# design.net
KiCad netlist of a schematic drawn in Altium Designer
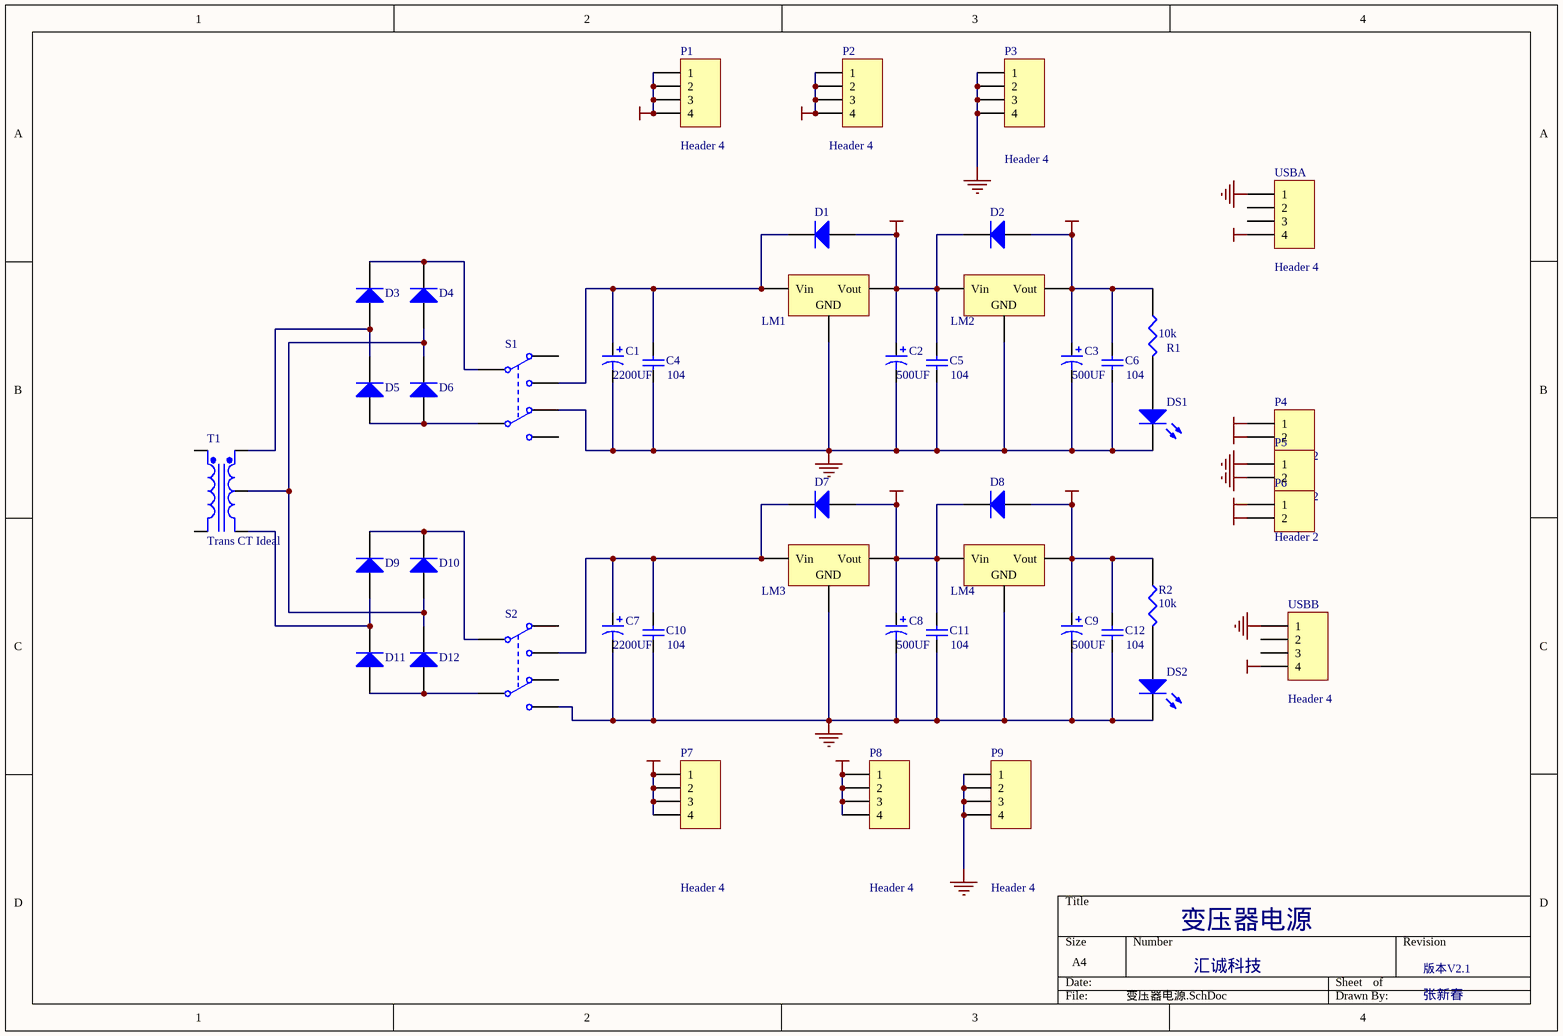
[diagram p0: 变压器电源.SchDoc]

(export (version "E")
  (design (tool "Eeschema 10.0.6"))
  (components
    (comp (ref "C1")
      (value "2200UF")
      (footprint "C 2200/50")
      (description "Polarized Capacitor (Radial)")
      (fields (field (name "PUBLISHER") "Altium Limited"))
      (libsource (lib "Miscellaneous Devices") (part "Cap Pol1"))
    )
    (comp (ref "C2")
      (value "500UF")
      (footprint "C 220/50")
      (description "Polarized Capacitor (Radial)")
      (fields (field (name "PUBLISHER") "Altium Limited"))
      (libsource (lib "Miscellaneous Devices") (part "Cap Pol1"))
    )
    (comp (ref "C3")
      (value "500UF")
      (footprint "C 220/50")
      (description "Polarized Capacitor (Radial)")
      (fields (field (name "PUBLISHER") "Altium Limited"))
      (libsource (lib "Miscellaneous Devices") (part "Cap Pol1"))
    )
    (comp (ref "C4")
      (value "104")
      (footprint "HDR1X2")
      (description "Capacitor")
      (fields (field (name "PUBLISHER") "Altium Limited"))
      (libsource (lib "Miscellaneous Devices") (part "Cap"))
    )
    (comp (ref "C5")
      (value "104")
      (footprint "HDR1X2")
      (description "Capacitor")
      (fields (field (name "PUBLISHER") "Altium Limited"))
      (libsource (lib "Miscellaneous Devices") (part "Cap"))
    )
    (comp (ref "C6")
      (value "104")
      (footprint "HDR1X2")
      (description "Capacitor")
      (fields (field (name "PUBLISHER") "Altium Limited"))
      (libsource (lib "Miscellaneous Devices") (part "Cap"))
    )
    (comp (ref "C7")
      (value "2200UF")
      (footprint "C 2200/50")
      (description "Polarized Capacitor (Radial)")
      (fields (field (name "PUBLISHER") "Altium Limited"))
      (libsource (lib "Miscellaneous Devices") (part "Cap Pol1"))
    )
    (comp (ref "C8")
      (value "500UF")
      (footprint "C 220/50")
      (description "Polarized Capacitor (Radial)")
      (fields (field (name "PUBLISHER") "Altium Limited"))
      (libsource (lib "Miscellaneous Devices") (part "Cap Pol1"))
    )
    (comp (ref "C9")
      (value "500UF")
      (footprint "C 220/50")
      (description "Polarized Capacitor (Radial)")
      (fields (field (name "PUBLISHER") "Altium Limited"))
      (libsource (lib "Miscellaneous Devices") (part "Cap Pol1"))
    )
    (comp (ref "C10")
      (value "104")
      (footprint "HDR1X2")
      (description "Capacitor")
      (fields (field (name "PUBLISHER") "Altium Limited"))
      (libsource (lib "Miscellaneous Devices") (part "Cap"))
    )
    (comp (ref "C11")
      (value "104")
      (footprint "HDR1X2")
      (description "Capacitor")
      (fields (field (name "PUBLISHER") "Altium Limited"))
      (libsource (lib "Miscellaneous Devices") (part "Cap"))
    )
    (comp (ref "C12")
      (value "104")
      (footprint "HDR1X2")
      (description "Capacitor")
      (fields (field (name "PUBLISHER") "Altium Limited"))
      (libsource (lib "Miscellaneous Devices") (part "Cap"))
    )
    (comp (ref "D1")
      (value "~")
      (footprint "DIO10.46-5.3x2.8")
      (description "1 Amp General Purpose Rectifier")
      (fields (field (name "PUBLISHER") "Altium Limited"))
      (libsource (lib "Miscellaneous Devices") (part "Diode 1N4007"))
    )
    (comp (ref "D2")
      (value "~")
      (footprint "DIO10.46-5.3x2.8")
      (description "1 Amp General Purpose Rectifier")
      (fields (field (name "PUBLISHER") "Altium Limited"))
      (libsource (lib "Miscellaneous Devices") (part "Diode 1N4007"))
    )
    (comp (ref "D3")
      (value "~")
      (footprint "DIO10.46-5.3x2.8")
      (description "1 Amp General Purpose Rectifier")
      (fields (field (name "PUBLISHER") "Altium Limited"))
      (libsource (lib "Miscellaneous Devices") (part "Diode 1N4007"))
    )
    (comp (ref "D4")
      (value "~")
      (footprint "DIO10.46-5.3x2.8")
      (description "1 Amp General Purpose Rectifier")
      (fields (field (name "PUBLISHER") "Altium Limited"))
      (libsource (lib "Miscellaneous Devices") (part "Diode 1N4007"))
    )
    (comp (ref "D5")
      (value "~")
      (footprint "DIO10.46-5.3x2.8")
      (description "1 Amp General Purpose Rectifier")
      (fields (field (name "PUBLISHER") "Altium Limited"))
      (libsource (lib "Miscellaneous Devices") (part "Diode 1N4007"))
    )
    (comp (ref "D6")
      (value "~")
      (footprint "DIO10.46-5.3x2.8")
      (description "1 Amp General Purpose Rectifier")
      (fields (field (name "PUBLISHER") "Altium Limited"))
      (libsource (lib "Miscellaneous Devices") (part "Diode 1N4007"))
    )
    (comp (ref "D7")
      (value "~")
      (footprint "DIO10.46-5.3x2.8")
      (description "1 Amp General Purpose Rectifier")
      (fields (field (name "PUBLISHER") "Altium Limited"))
      (libsource (lib "Miscellaneous Devices") (part "Diode 1N4007"))
    )
    (comp (ref "D8")
      (value "~")
      (footprint "DIO10.46-5.3x2.8")
      (description "1 Amp General Purpose Rectifier")
      (fields (field (name "PUBLISHER") "Altium Limited"))
      (libsource (lib "Miscellaneous Devices") (part "Diode 1N4007"))
    )
    (comp (ref "D9")
      (value "~")
      (footprint "DIO10.46-5.3x2.8")
      (description "1 Amp General Purpose Rectifier")
      (fields (field (name "PUBLISHER") "Altium Limited"))
      (libsource (lib "Miscellaneous Devices") (part "Diode 1N4007"))
    )
    (comp (ref "D10")
      (value "~")
      (footprint "DIO10.46-5.3x2.8")
      (description "1 Amp General Purpose Rectifier")
      (fields (field (name "PUBLISHER") "Altium Limited"))
      (libsource (lib "Miscellaneous Devices") (part "Diode 1N4007"))
    )
    (comp (ref "D11")
      (value "~")
      (footprint "DIO10.46-5.3x2.8")
      (description "1 Amp General Purpose Rectifier")
      (fields (field (name "PUBLISHER") "Altium Limited"))
      (libsource (lib "Miscellaneous Devices") (part "Diode 1N4007"))
    )
    (comp (ref "D12")
      (value "~")
      (footprint "DIO10.46-5.3x2.8")
      (description "1 Amp General Purpose Rectifier")
      (fields (field (name "PUBLISHER") "Altium Limited"))
      (libsource (lib "Miscellaneous Devices") (part "Diode 1N4007"))
    )
    (comp (ref "DS1")
      (value "~")
      (footprint "HDR1X2")
      (description "Typical INFRARED GaAs LED")
      (fields (field (name "PUBLISHER") "Altium Limited"))
      (libsource (lib "Miscellaneous Devices") (part "LED0"))
    )
    (comp (ref "DS2")
      (value "~")
      (footprint "HDR1X2")
      (description "Typical INFRARED GaAs LED")
      (fields (field (name "PUBLISHER") "Altium Limited"))
      (libsource (lib "Miscellaneous Devices") (part "LED0"))
    )
    (comp (ref "LM1")
      (value "~")
      (footprint "wyk")
      (description "Voltage Regulator")
      (fields (field (name "PUBLISHER") "Altium Limited"))
      (libsource (lib "Miscellaneous Devices") (part "Volt Reg"))
    )
    (comp (ref "LM2")
      (value "~")
      (footprint "wyk")
      (description "Voltage Regulator")
      (fields (field (name "PUBLISHER") "Altium Limited"))
      (libsource (lib "Miscellaneous Devices") (part "Volt Reg"))
    )
    (comp (ref "LM3")
      (value "~")
      (footprint "wyk")
      (description "Voltage Regulator")
      (fields (field (name "PUBLISHER") "Altium Limited"))
      (libsource (lib "Miscellaneous Devices") (part "Volt Reg"))
    )
    (comp (ref "LM4")
      (value "~")
      (footprint "wyk")
      (description "Voltage Regulator")
      (fields (field (name "PUBLISHER") "Altium Limited"))
      (libsource (lib "Miscellaneous Devices") (part "Volt Reg"))
    )
    (comp (ref "P1")
      (value "Header 4")
      (footprint "HDR1X4")
      (description "Header, 4-Pin")
      (fields (field (name "PUBLISHER") "Altium Limited"))
      (libsource (lib "Miscellaneous Connectors") (part "Header 4"))
    )
    (comp (ref "P2")
      (value "Header 4")
      (footprint "HDR1X4")
      (description "Header, 4-Pin")
      (fields (field (name "PUBLISHER") "Altium Limited"))
      (libsource (lib "Miscellaneous Connectors") (part "Header 4"))
    )
    (comp (ref "P3")
      (value "Header 4")
      (footprint "HDR1X4")
      (description "Header, 4-Pin")
      (fields (field (name "PUBLISHER") "Altium Limited"))
      (libsource (lib "Miscellaneous Connectors") (part "Header 4"))
    )
    (comp (ref "P4")
      (value "Header 2")
      (footprint "PCBComponent_1")
      (description "Header, 2-Pin")
      (fields (field (name "PUBLISHER") "Altium Limited"))
      (libsource (lib "Miscellaneous Connectors") (part "Header 2"))
    )
    (comp (ref "P5")
      (value "Header 2")
      (footprint "PCBComponent_1")
      (description "Header, 2-Pin")
      (fields (field (name "PUBLISHER") "Altium Limited"))
      (libsource (lib "Miscellaneous Connectors") (part "Header 2"))
    )
    (comp (ref "P6")
      (value "Header 2")
      (footprint "PCBComponent_1")
      (description "Header, 2-Pin")
      (fields (field (name "PUBLISHER") "Altium Limited"))
      (libsource (lib "Miscellaneous Connectors") (part "Header 2"))
    )
    (comp (ref "P7")
      (value "Header 4")
      (footprint "HDR1X4")
      (description "Header, 4-Pin")
      (fields (field (name "PUBLISHER") "Altium Limited"))
      (libsource (lib "Miscellaneous Connectors") (part "Header 4"))
    )
    (comp (ref "P8")
      (value "Header 4")
      (footprint "HDR1X4")
      (description "Header, 4-Pin")
      (fields (field (name "PUBLISHER") "Altium Limited"))
      (libsource (lib "Miscellaneous Connectors") (part "Header 4"))
    )
    (comp (ref "P9")
      (value "Header 4")
      (footprint "HDR1X4")
      (description "Header, 4-Pin")
      (fields (field (name "PUBLISHER") "Altium Limited"))
      (libsource (lib "Miscellaneous Connectors") (part "Header 4"))
    )
    (comp (ref "R1") (value "10k") (footprint "HDR1X2") (libsource (lib "*") (part "RES1")))
    (comp (ref "R2") (value "10k") (footprint "HDR1X2") (libsource (lib "*") (part "RES1")))
    (comp (ref "S1")
      (value "~")
      (footprint "DPDT-6")
      (description "Switch")
      (fields (field (name "PUBLISHER") "Altium Limited"))
      (libsource (lib "Miscellaneous Devices") (part "SW DPDT"))
    )
    (comp (ref "S2")
      (value "~")
      (footprint "DPDT-6")
      (description "Switch")
      (fields (field (name "PUBLISHER") "Altium Limited"))
      (libsource (lib "Miscellaneous Devices") (part "SW DPDT"))
    )
    (comp (ref "T1")
      (value "Trans CT Ideal")
      (footprint "T")
      (description "Center-Tapped Transformer (Ideal)")
      (fields (field (name "PUBLISHER") "Altium Limited"))
      (libsource (lib "Miscellaneous Devices") (part "Trans CT Ideal"))
    )
    (comp (ref "USBA")
      (value "Header 4")
      (footprint "HDR1X4")
      (description "Header, 4-Pin")
      (fields (field (name "PUBLISHER") "Altium Limited"))
      (libsource (lib "Miscellaneous Connectors") (part "Header 4"))
    )
    (comp (ref "USBB")
      (value "Header 4")
      (footprint "HDR1X4")
      (description "Header, 4-Pin")
      (fields (field (name "PUBLISHER") "Altium Limited"))
      (libsource (lib "Miscellaneous Connectors") (part "Header 4"))
    )
  )
  (nets
    (net (code "1") (name "A05") (class "Default")
      (node (ref "C3") (pin "1") (pinfunction "1_1") (pintype "passive"))
      (node (ref "C6") (pin "2") (pinfunction "2_2") (pintype "passive"))
      (node (ref "D2") (pin "1") (pinfunction "A_1") (pintype "passive"))
      (node (ref "LM2") (pin "3") (pinfunction "Vout_3") (pintype "passive"))
      (node (ref "P2") (pin "1") (pinfunction "1_1") (pintype "passive"))
      (node (ref "P2") (pin "2") (pinfunction "2_2") (pintype "passive"))
      (node (ref "P2") (pin "3") (pinfunction "3_3") (pintype "passive"))
      (node (ref "P2") (pin "4") (pinfunction "4_4") (pintype "passive"))
      (node (ref "P4") (pin "2") (pinfunction "2_2") (pintype "passive"))
      (node (ref "R1") (pin "1") (pinfunction "1_1") (pintype "passive"))
      (node (ref "USBA") (pin "4") (pinfunction "4_4") (pintype "passive"))
    )
    (net (code "2") (name "A12") (class "Default")
      (node (ref "C2") (pin "1") (pinfunction "1_1") (pintype "passive"))
      (node (ref "C5") (pin "2") (pinfunction "2_2") (pintype "passive"))
      (node (ref "D1") (pin "1") (pinfunction "A_1") (pintype "passive"))
      (node (ref "D2") (pin "2") (pinfunction "K_2") (pintype "passive"))
      (node (ref "LM1") (pin "3") (pinfunction "Vout_3") (pintype "passive"))
      (node (ref "LM2") (pin "1") (pinfunction "Vin_1") (pintype "passive"))
      (node (ref "P1") (pin "1") (pinfunction "1_1") (pintype "passive"))
      (node (ref "P1") (pin "2") (pinfunction "2_2") (pintype "passive"))
      (node (ref "P1") (pin "3") (pinfunction "3_3") (pintype "passive"))
      (node (ref "P1") (pin "4") (pinfunction "4_4") (pintype "passive"))
      (node (ref "P4") (pin "1") (pinfunction "1_1") (pintype "passive"))
    )
    (net (code "3") (name "AGND") (class "Default")
      (node (ref "C1") (pin "2") (pinfunction "2_2") (pintype "passive"))
      (node (ref "C2") (pin "2") (pinfunction "2_2") (pintype "passive"))
      (node (ref "C3") (pin "2") (pinfunction "2_2") (pintype "passive"))
      (node (ref "C4") (pin "1") (pinfunction "1_1") (pintype "passive"))
      (node (ref "C5") (pin "1") (pinfunction "1_1") (pintype "passive"))
      (node (ref "C6") (pin "1") (pinfunction "1_1") (pintype "passive"))
      (node (ref "DS1") (pin "2") (pinfunction "K_2") (pintype "passive"))
      (node (ref "LM1") (pin "2") (pinfunction "GND_2") (pintype "passive"))
      (node (ref "LM2") (pin "2") (pinfunction "GND_2") (pintype "passive"))
      (node (ref "P3") (pin "1") (pinfunction "1_1") (pintype "passive"))
      (node (ref "P3") (pin "2") (pinfunction "2_2") (pintype "passive"))
      (node (ref "P3") (pin "3") (pinfunction "3_3") (pintype "passive"))
      (node (ref "P3") (pin "4") (pinfunction "4_4") (pintype "passive"))
      (node (ref "P5") (pin "2") (pinfunction "2_2") (pintype "passive"))
      (node (ref "S1") (pin "4") (pinfunction "NC2_4") (pintype "passive"))
      (node (ref "USBB") (pin "1") (pinfunction "1_1") (pintype "passive"))
    )
    (net (code "4") (name "B05") (class "Default")
      (node (ref "C12") (pin "2") (pinfunction "2_2") (pintype "passive"))
      (node (ref "C9") (pin "1") (pinfunction "1_1") (pintype "passive"))
      (node (ref "D8") (pin "1") (pinfunction "A_1") (pintype "passive"))
      (node (ref "LM4") (pin "3") (pinfunction "Vout_3") (pintype "passive"))
      (node (ref "P6") (pin "1") (pinfunction "1_1") (pintype "passive"))
      (node (ref "P8") (pin "1") (pinfunction "1_1") (pintype "passive"))
      (node (ref "P8") (pin "2") (pinfunction "2_2") (pintype "passive"))
      (node (ref "P8") (pin "3") (pinfunction "3_3") (pintype "passive"))
      (node (ref "P8") (pin "4") (pinfunction "4_4") (pintype "passive"))
      (node (ref "R2") (pin "1") (pinfunction "1_1") (pintype "passive"))
      (node (ref "USBB") (pin "4") (pinfunction "4_4") (pintype "passive"))
    )
    (net (code "5") (name "B12") (class "Default")
      (node (ref "C11") (pin "2") (pinfunction "2_2") (pintype "passive"))
      (node (ref "C8") (pin "1") (pinfunction "1_1") (pintype "passive"))
      (node (ref "D7") (pin "1") (pinfunction "A_1") (pintype "passive"))
      (node (ref "D8") (pin "2") (pinfunction "K_2") (pintype "passive"))
      (node (ref "LM3") (pin "3") (pinfunction "Vout_3") (pintype "passive"))
      (node (ref "LM4") (pin "1") (pinfunction "Vin_1") (pintype "passive"))
      (node (ref "P6") (pin "2") (pinfunction "2_2") (pintype "passive"))
      (node (ref "P7") (pin "1") (pinfunction "1_1") (pintype "passive"))
      (node (ref "P7") (pin "2") (pinfunction "2_2") (pintype "passive"))
      (node (ref "P7") (pin "3") (pinfunction "3_3") (pintype "passive"))
      (node (ref "P7") (pin "4") (pinfunction "4_4") (pintype "passive"))
    )
    (net (code "6") (name "BGND") (class "Default")
      (node (ref "C10") (pin "1") (pinfunction "1_1") (pintype "passive"))
      (node (ref "C11") (pin "1") (pinfunction "1_1") (pintype "passive"))
      (node (ref "C12") (pin "1") (pinfunction "1_1") (pintype "passive"))
      (node (ref "C7") (pin "2") (pinfunction "2_2") (pintype "passive"))
      (node (ref "C8") (pin "2") (pinfunction "2_2") (pintype "passive"))
      (node (ref "C9") (pin "2") (pinfunction "2_2") (pintype "passive"))
      (node (ref "DS2") (pin "2") (pinfunction "K_2") (pintype "passive"))
      (node (ref "LM3") (pin "2") (pinfunction "GND_2") (pintype "passive"))
      (node (ref "LM4") (pin "2") (pinfunction "GND_2") (pintype "passive"))
      (node (ref "P5") (pin "1") (pinfunction "1_1") (pintype "passive"))
      (node (ref "P9") (pin "1") (pinfunction "1_1") (pintype "passive"))
      (node (ref "P9") (pin "2") (pinfunction "2_2") (pintype "passive"))
      (node (ref "P9") (pin "3") (pinfunction "3_3") (pintype "passive"))
      (node (ref "P9") (pin "4") (pinfunction "4_4") (pintype "passive"))
      (node (ref "S2") (pin "6") (pinfunction "NO2_6") (pintype "passive"))
      (node (ref "USBA") (pin "1") (pinfunction "1_1") (pintype "passive"))
    )
    (net (code "7") (name "Net-(D1-K)") (class "Default")
      (node (ref "C1") (pin "1") (pinfunction "1_1") (pintype "passive"))
      (node (ref "C4") (pin "2") (pinfunction "2_2") (pintype "passive"))
      (node (ref "D1") (pin "2") (pinfunction "K_2") (pintype "passive"))
      (node (ref "LM1") (pin "1") (pinfunction "Vin_1") (pintype "passive"))
      (node (ref "S1") (pin "3") (pinfunction "NO1_3") (pintype "passive"))
    )
    (net (code "8") (name "Net-(D3-A)") (class "Default")
      (node (ref "D3") (pin "1") (pinfunction "A_1") (pintype "passive"))
      (node (ref "D5") (pin "2") (pinfunction "K_2") (pintype "passive"))
      (node (ref "T1") (pin "3") (pinfunction "Sec+_3") (pintype "passive"))
    )
    (net (code "9") (name "Net-(D3-K)") (class "Default")
      (node (ref "D3") (pin "2") (pinfunction "K_2") (pintype "passive"))
      (node (ref "D4") (pin "2") (pinfunction "K_2") (pintype "passive"))
      (node (ref "S1") (pin "1") (pinfunction "COMMON1_1") (pintype "passive"))
    )
    (net (code "10") (name "Net-(D5-A)") (class "Default")
      (node (ref "D5") (pin "1") (pinfunction "A_1") (pintype "passive"))
      (node (ref "D6") (pin "1") (pinfunction "A_1") (pintype "passive"))
      (node (ref "S1") (pin "5") (pinfunction "COMMON2_5") (pintype "passive"))
    )
    (net (code "11") (name "Net-(D7-K)") (class "Default")
      (node (ref "C10") (pin "2") (pinfunction "2_2") (pintype "passive"))
      (node (ref "C7") (pin "1") (pinfunction "1_1") (pintype "passive"))
      (node (ref "D7") (pin "2") (pinfunction "K_2") (pintype "passive"))
      (node (ref "LM3") (pin "1") (pinfunction "Vin_1") (pintype "passive"))
      (node (ref "S2") (pin "3") (pinfunction "NO1_3") (pintype "passive"))
    )
    (net (code "12") (name "Net-(D10-A)") (class "Default")
      (node (ref "D10") (pin "1") (pinfunction "A_1") (pintype "passive"))
      (node (ref "D12") (pin "2") (pinfunction "K_2") (pintype "passive"))
      (node (ref "D4") (pin "1") (pinfunction "A_1") (pintype "passive"))
      (node (ref "D6") (pin "2") (pinfunction "K_2") (pintype "passive"))
      (node (ref "T1") (pin "4") (pinfunction "SecCT_4") (pintype "passive"))
    )
    (net (code "13") (name "Net-(D10-K)") (class "Default")
      (node (ref "D10") (pin "2") (pinfunction "K_2") (pintype "passive"))
      (node (ref "D9") (pin "2") (pinfunction "K_2") (pintype "passive"))
      (node (ref "S2") (pin "1") (pinfunction "COMMON1_1") (pintype "passive"))
    )
    (net (code "14") (name "Net-(D11-A)") (class "Default")
      (node (ref "D11") (pin "1") (pinfunction "A_1") (pintype "passive"))
      (node (ref "D12") (pin "1") (pinfunction "A_1") (pintype "passive"))
      (node (ref "S2") (pin "5") (pinfunction "COMMON2_5") (pintype "passive"))
    )
    (net (code "15") (name "Net-(D11-K)") (class "Default")
      (node (ref "D11") (pin "2") (pinfunction "K_2") (pintype "passive"))
      (node (ref "D9") (pin "1") (pinfunction "A_1") (pintype "passive"))
      (node (ref "T1") (pin "5") (pinfunction "Sec-_5") (pintype "passive"))
    )
    (net (code "16") (name "Net-(DS1-A)") (class "Default")
      (node (ref "DS1") (pin "1") (pinfunction "A_1") (pintype "passive"))
      (node (ref "R1") (pin "2") (pinfunction "2_2") (pintype "passive"))
    )
    (net (code "17") (name "Net-(DS2-A)") (class "Default")
      (node (ref "DS2") (pin "1") (pinfunction "A_1") (pintype "passive"))
      (node (ref "R2") (pin "2") (pinfunction "2_2") (pintype "passive"))
    )
    (net (code "18") (name "unconnected-(S1-NC1-Pad2)") (class "Default")
      (node (ref "S1") (pin "2") (pinfunction "NC1_2") (pintype "passive"))
    )
    (net (code "19") (name "unconnected-(S1-NO2-Pad6)") (class "Default")
      (node (ref "S1") (pin "6") (pinfunction "NO2_6") (pintype "passive"))
    )
    (net (code "20") (name "unconnected-(S2-NC1-Pad2)") (class "Default")
      (node (ref "S2") (pin "2") (pinfunction "NC1_2") (pintype "passive"))
    )
    (net (code "21") (name "unconnected-(S2-NC2-Pad4)") (class "Default")
      (node (ref "S2") (pin "4") (pinfunction "NC2_4") (pintype "passive"))
    )
    (net (code "22") (name "unconnected-(T1-Pri+-Pad1)") (class "Default")
      (node (ref "T1") (pin "1") (pinfunction "Pri+_1") (pintype "passive"))
    )
    (net (code "23") (name "unconnected-(T1-Pri--Pad2)") (class "Default")
      (node (ref "T1") (pin "2") (pinfunction "Pri-_2") (pintype "passive"))
    )
    (net (code "24") (name "unconnected-(USBA-Pad2)") (class "Default")
      (node (ref "USBA") (pin "2") (pinfunction "2_2") (pintype "passive"))
    )
    (net (code "25") (name "unconnected-(USBA-Pad3)") (class "Default")
      (node (ref "USBA") (pin "3") (pinfunction "3_3") (pintype "passive"))
    )
    (net (code "26") (name "unconnected-(USBB-Pad2)") (class "Default")
      (node (ref "USBB") (pin "2") (pinfunction "2_2") (pintype "passive"))
    )
    (net (code "27") (name "unconnected-(USBB-Pad3)") (class "Default")
      (node (ref "USBB") (pin "3") (pinfunction "3_3") (pintype "passive"))
    )
  )
)
